# ADC.net
KiCad netlist of a schematic drawn in Altium Designer
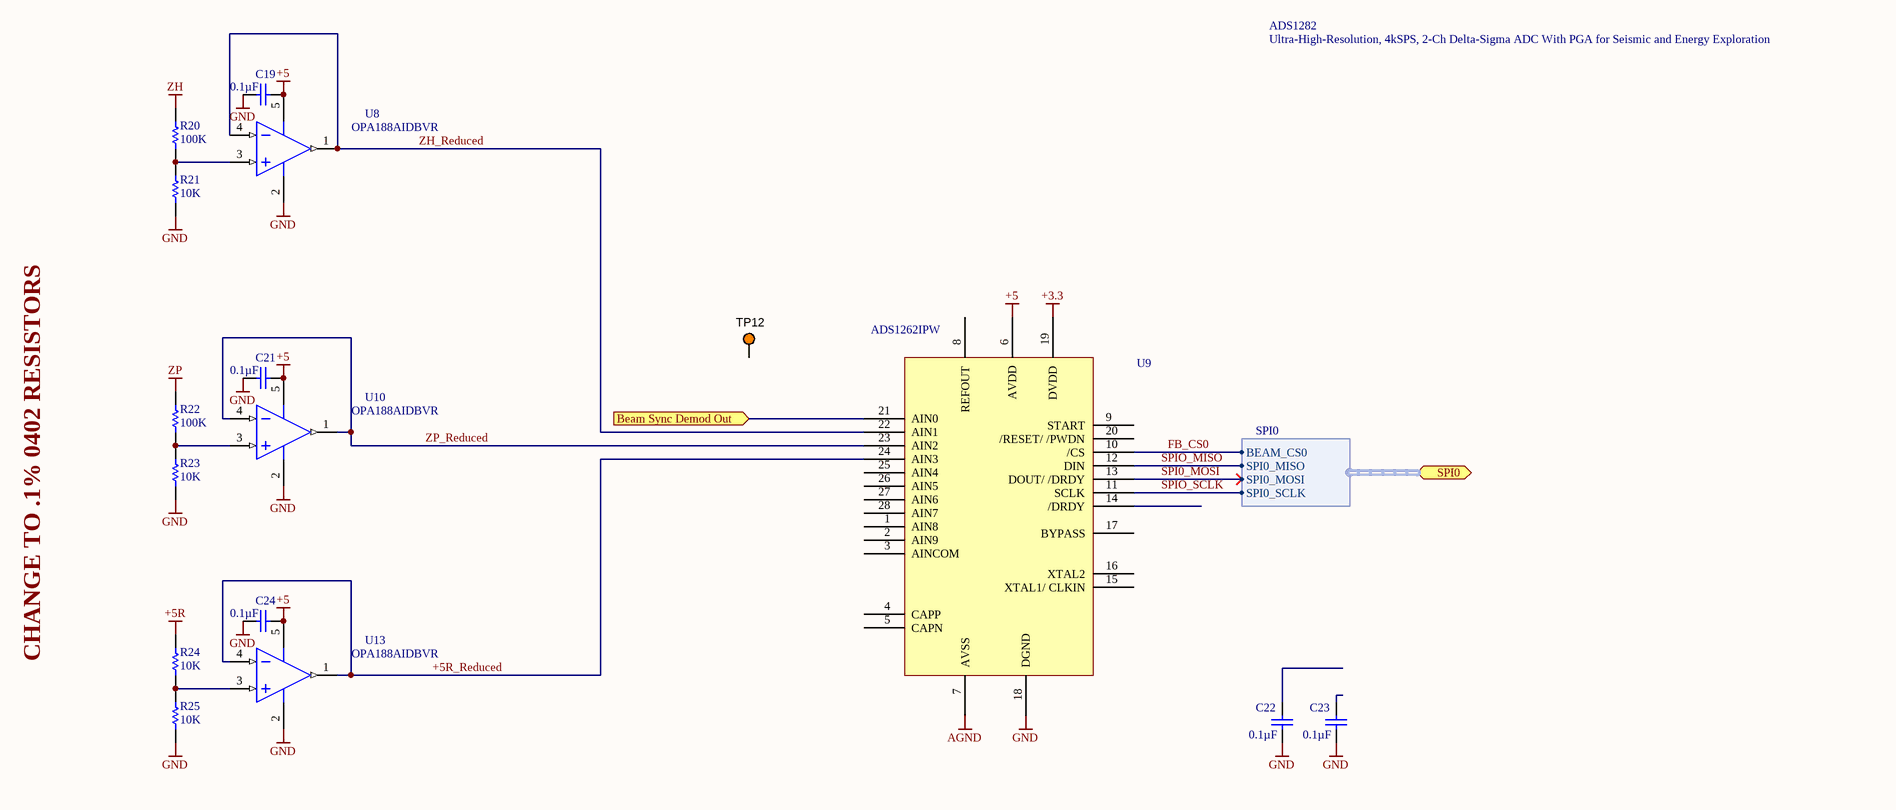
[diagram p0: ADC.SchDoc]

(export (version "E")
  (design (tool "Eeschema 10.0.6"))
  (components
    (comp (ref "C19")
      (value "CAP CER 0.1UF 25V X7R 0805")
      (footprint "CAPC0805(2012)145_N")
      (fields
        (field (name "MANUFACTURER") "Murata Electronics North America")
        (field (name "MANUFACTURER PART NUMBER") "GRM21BR71E104KA01L")
        (field (name "CAPACITANCE") "0.1µF")
        (field (name "TOLERANCE") "±10%")
      )
      (libsource (lib "Altium Content Vault") (part "CMP-1036-04795-1"))
    )
    (comp (ref "C21")
      (value "CAP CER 0.1UF 25V X7R 0805")
      (footprint "CAPC0805(2012)145_N")
      (fields
        (field (name "MANUFACTURER") "Murata Electronics North America")
        (field (name "MANUFACTURER PART NUMBER") "GRM21BR71E104KA01L")
        (field (name "CAPACITANCE") "0.1µF")
        (field (name "TOLERANCE") "±10%")
      )
      (libsource (lib "Altium Content Vault") (part "CMP-1036-04795-1"))
    )
    (comp (ref "C22")
      (value "CAP CER 0.1UF 25V X7R 0805")
      (footprint "CAPC0805(2012)145_N")
      (fields
        (field (name "MANUFACTURER") "Murata Electronics North America")
        (field (name "MANUFACTURER PART NUMBER") "GRM21BR71E104KA01L")
        (field (name "CAPACITANCE") "0.1µF")
        (field (name "TOLERANCE") "±10%")
      )
      (libsource (lib "Altium Content Vault") (part "CMP-1036-04795-1"))
    )
    (comp (ref "C23")
      (value "CAP CER 0.1UF 25V X7R 0805")
      (footprint "CAPC0805(2012)145_N")
      (fields
        (field (name "MANUFACTURER") "Murata Electronics North America")
        (field (name "MANUFACTURER PART NUMBER") "GRM21BR71E104KA01L")
        (field (name "CAPACITANCE") "0.1µF")
        (field (name "TOLERANCE") "±10%")
      )
      (libsource (lib "Altium Content Vault") (part "CMP-1036-04795-1"))
    )
    (comp (ref "C24")
      (value "CAP CER 0.1UF 25V X7R 0805")
      (footprint "CAPC0805(2012)145_N")
      (fields
        (field (name "MANUFACTURER") "Murata Electronics North America")
        (field (name "MANUFACTURER PART NUMBER") "GRM21BR71E104KA01L")
        (field (name "CAPACITANCE") "0.1µF")
        (field (name "TOLERANCE") "±10%")
      )
      (libsource (lib "Altium Content Vault") (part "CMP-1036-04795-1"))
    )
    (comp (ref "R20")
      (value "100K")
      (footprint "RESC0805(2012)_L")
      (description "RES SMD 100K OHM 1% 1/8W 0805")
      (fields
        (field (name "MANUFACTURER") "Vishay Dale")
        (field (name "MANUFACTURER PART NUMBER") "RCA0805100KFKEA")
      )
      (libsource (lib "Altium Content Vault") (part "CMP-1013-00215-1"))
    )
    (comp (ref "R21")
      (value "10K")
      (footprint "RESC0805(2012)_L")
      (description "RES SMD 10K OHM 1% 1/8W 0805")
      (fields
        (field (name "MANUFACTURER") "Vishay Dale")
        (field (name "MANUFACTURER PART NUMBER") "CRCW080510K0FKEA")
      )
      (libsource (lib "Altium Content Vault") (part "CMP-1013-00215-1"))
    )
    (comp (ref "R22")
      (value "100K")
      (footprint "RESC0805(2012)_L")
      (description "RES SMD 100K OHM 1% 1/8W 0805")
      (fields
        (field (name "MANUFACTURER") "Vishay Dale")
        (field (name "MANUFACTURER PART NUMBER") "RCA0805100KFKEA")
      )
      (libsource (lib "Altium Content Vault") (part "CMP-1013-00215-1"))
    )
    (comp (ref "R23")
      (value "10K")
      (footprint "RESC0805(2012)_L")
      (description "RES SMD 10K OHM 1% 1/8W 0805")
      (fields
        (field (name "MANUFACTURER") "Vishay Dale")
        (field (name "MANUFACTURER PART NUMBER") "CRCW080510K0FKEA")
      )
      (libsource (lib "Altium Content Vault") (part "CMP-1013-00215-1"))
    )
    (comp (ref "R24")
      (value "10K")
      (footprint "RESC0805(2012)_L")
      (description "RES SMD 10K OHM 1% 1/8W 0805")
      (fields
        (field (name "MANUFACTURER") "Vishay Dale")
        (field (name "MANUFACTURER PART NUMBER") "CRCW080510K0FKEA")
      )
      (libsource (lib "Altium Content Vault") (part "CMP-1013-00215-1"))
    )
    (comp (ref "R25")
      (value "10K")
      (footprint "RESC0805(2012)_L")
      (description "RES SMD 10K OHM 1% 1/8W 0805")
      (fields
        (field (name "MANUFACTURER") "Vishay Dale")
        (field (name "MANUFACTURER PART NUMBER") "CRCW080510K0FKEA")
      )
      (libsource (lib "Altium Content Vault") (part "CMP-1013-00215-1"))
    )
    (comp (ref "TP12")
      (value "5003")
      (footprint "KSTN-5003")
      (description "Test Point, Orange, 1-Pin THD, RoHS")
      (libsource (lib "Altium Content Vault") (part "CMP-1672-00009-1"))
    )
    (comp (ref "U8")
      (value "OPA188AIDBVR")
      (footprint "DBV0005A_M")
      (fields (field (name "MANUFACTURER") "Texas Instruments"))
      (libsource (lib "Altium Content Vault") (part "CMP-0809-00005-2"))
    )
    (comp (ref "U9")
      (value "ADS1262")
      (footprint "ADS1262")
      (description "32 bit Analog to Digital Converter")
      (fields
        (field (name "SUPPLIER PART NUMBER 1") "ADS1262IPW")
        (field (name "MANUFACTURER") "Texas Instruments")
        (field (name "MANUFACTURER PART NUMBER") "ADS1262IPW")
      )
      (libsource (lib "ZLS_Schematic_lib") (part "ADS1262"))
    )
    (comp (ref "U10")
      (value "OPA188AIDBVR")
      (footprint "DBV0005A_M")
      (fields (field (name "MANUFACTURER") "Texas Instruments"))
      (libsource (lib "Altium Content Vault") (part "CMP-0809-00005-2"))
    )
    (comp (ref "U13")
      (value "OPA188AIDBVR")
      (footprint "DBV0005A_M")
      (fields (field (name "MANUFACTURER") "Texas Instruments"))
      (libsource (lib "Altium Content Vault") (part "CMP-0809-00005-2"))
    )
  )
  (nets
    (net (code "2") (name "+3.3") (class "Default")
      (node (ref "U9") (pin "19") (pinfunction "DVDD_19") (pintype "passive"))
    )
    (net (code "3") (name "+5") (class "Default")
      (node (ref "C19") (pin "2") (pinfunction "2_2") (pintype "passive"))
      (node (ref "C21") (pin "2") (pinfunction "2_2") (pintype "passive"))
      (node (ref "C24") (pin "2") (pinfunction "2_2") (pintype "passive"))
      (node (ref "U10") (pin "5") (pinfunction "V+_5") (pintype "power_in"))
      (node (ref "U13") (pin "5") (pinfunction "V+_5") (pintype "power_in"))
      (node (ref "U8") (pin "5") (pinfunction "V+_5") (pintype "power_in"))
      (node (ref "U9") (pin "6") (pinfunction "AVDD_6") (pintype "passive"))
    )
    (net (code "4") (name "+5R") (class "Default")
      (node (ref "R24") (pin "2") (pinfunction "2_2") (pintype "passive"))
    )
    (net (code "5") (name "/+5R_Reduced") (class "Default")
      (node (ref "U13") (pin "1") (pinfunction "OUT_1") (pintype "output"))
      (node (ref "U13") (pin "4") (pinfunction "IN-_4") (pintype "input"))
      (node (ref "U9") (pin "24") (pinfunction "AIN3_24") (pintype "passive"))
    )
    (net (code "6") (name "/Beam Sync Demod Out") (class "Default")
      (node (ref "U9") (pin "21") (pinfunction "AIN0_21") (pintype "passive"))
    )
    (net (code "7") (name "/FB_CS0") (class "Default")
      (node (ref "U9") (pin "10") (pinfunction "/CS_10") (pintype "passive"))
    )
    (net (code "8") (name "/SPI0_MOSI") (class "Default")
      (node (ref "U9") (pin "13") (pinfunction "DOUT/_/DRDY_13") (pintype "passive+no_connect"))
    )
    (net (code "9") (name "/SPIO_MISO") (class "Default")
      (node (ref "U9") (pin "12") (pinfunction "DIN_12") (pintype "passive"))
    )
    (net (code "10") (name "/SPIO_SCLK") (class "Default")
      (node (ref "U9") (pin "11") (pinfunction "SCLK_11") (pintype "passive"))
    )
    (net (code "11") (name "/ZH_Reduced") (class "Default")
      (node (ref "U8") (pin "1") (pinfunction "OUT_1") (pintype "output"))
      (node (ref "U8") (pin "4") (pinfunction "IN-_4") (pintype "input"))
      (node (ref "U9") (pin "22") (pinfunction "AIN1_22") (pintype "passive"))
    )
    (net (code "12") (name "/ZP_Reduced") (class "Default")
      (node (ref "U10") (pin "1") (pinfunction "OUT_1") (pintype "output"))
      (node (ref "U10") (pin "4") (pinfunction "IN-_4") (pintype "input"))
      (node (ref "U9") (pin "23") (pinfunction "AIN2_23") (pintype "passive"))
    )
    (net (code "14") (name "AGND") (class "Default")
      (node (ref "U9") (pin "7") (pinfunction "AVSS_7") (pintype "passive"))
    )
    (net (code "15") (name "GND") (class "Default")
      (node (ref "C19") (pin "1") (pinfunction "1_1") (pintype "passive"))
      (node (ref "C21") (pin "1") (pinfunction "1_1") (pintype "passive"))
      (node (ref "C22") (pin "2") (pinfunction "2_2") (pintype "passive"))
      (node (ref "C23") (pin "2") (pinfunction "2_2") (pintype "passive"))
      (node (ref "C24") (pin "1") (pinfunction "1_1") (pintype "passive"))
      (node (ref "R21") (pin "1") (pinfunction "1_1") (pintype "passive"))
      (node (ref "R23") (pin "1") (pinfunction "1_1") (pintype "passive"))
      (node (ref "R25") (pin "1") (pinfunction "1_1") (pintype "passive"))
      (node (ref "U10") (pin "2") (pinfunction "V-_2") (pintype "power_in"))
      (node (ref "U13") (pin "2") (pinfunction "V-_2") (pintype "power_in"))
      (node (ref "U8") (pin "2") (pinfunction "V-_2") (pintype "power_in"))
      (node (ref "U9") (pin "18") (pinfunction "DGND_18") (pintype "passive"))
    )
    (net (code "16") (name "Net-(U8-IN+)") (class "Default")
      (node (ref "R20") (pin "1") (pinfunction "1_1") (pintype "passive"))
      (node (ref "R21") (pin "2") (pinfunction "2_2") (pintype "passive"))
      (node (ref "U8") (pin "3") (pinfunction "IN+_3") (pintype "input"))
    )
    (net (code "17") (name "Net-(U10-IN+)") (class "Default")
      (node (ref "R22") (pin "1") (pinfunction "1_1") (pintype "passive"))
      (node (ref "R23") (pin "2") (pinfunction "2_2") (pintype "passive"))
      (node (ref "U10") (pin "3") (pinfunction "IN+_3") (pintype "input"))
    )
    (net (code "18") (name "Net-(U13-IN+)") (class "Default")
      (node (ref "R24") (pin "1") (pinfunction "1_1") (pintype "passive"))
      (node (ref "R25") (pin "2") (pinfunction "2_2") (pintype "passive"))
      (node (ref "U13") (pin "3") (pinfunction "IN+_3") (pintype "input"))
    )
    (net (code "19") (name "ZH") (class "Default")
      (node (ref "R20") (pin "2") (pinfunction "2_2") (pintype "passive"))
    )
    (net (code "20") (name "ZP") (class "Default")
      (node (ref "R22") (pin "2") (pinfunction "2_2") (pintype "passive"))
    )
    (net (code "21") (name "unconnected-(C22-Pad1)") (class "Default")
      (node (ref "C22") (pin "1") (pinfunction "1_1") (pintype "passive"))
    )
    (net (code "22") (name "unconnected-(C23-Pad1)") (class "Default")
      (node (ref "C23") (pin "1") (pinfunction "1_1") (pintype "passive"))
    )
    (net (code "23") (name "unconnected-(TP12-Pad1)") (class "Default")
      (node (ref "TP12") (pin "1") (pinfunction "1_1") (pintype "passive"))
    )
    (net (code "24") (name "unconnected-(U9-AIN4-Pad25)") (class "Default")
      (node (ref "U9") (pin "25") (pinfunction "AIN4_25") (pintype "passive"))
    )
    (net (code "25") (name "unconnected-(U9-AIN5-Pad26)") (class "Default")
      (node (ref "U9") (pin "26") (pinfunction "AIN5_26") (pintype "passive"))
    )
    (net (code "26") (name "unconnected-(U9-AIN6-Pad27)") (class "Default")
      (node (ref "U9") (pin "27") (pinfunction "AIN6_27") (pintype "passive"))
    )
    (net (code "27") (name "unconnected-(U9-AIN7-Pad28)") (class "Default")
      (node (ref "U9") (pin "28") (pinfunction "AIN7_28") (pintype "passive"))
    )
    (net (code "28") (name "unconnected-(U9-AIN8-Pad1)") (class "Default")
      (node (ref "U9") (pin "1") (pinfunction "AIN8_1") (pintype "passive"))
    )
    (net (code "29") (name "unconnected-(U9-AIN9-Pad2)") (class "Default")
      (node (ref "U9") (pin "2") (pinfunction "AIN9_2") (pintype "passive"))
    )
    (net (code "30") (name "unconnected-(U9-AINCOM-Pad3)") (class "Default")
      (node (ref "U9") (pin "3") (pinfunction "AINCOM_3") (pintype "passive"))
    )
    (net (code "31") (name "unconnected-(U9-BYPASS-Pad17)") (class "Default")
      (node (ref "U9") (pin "17") (pinfunction "BYPASS_17") (pintype "passive"))
    )
    (net (code "32") (name "unconnected-(U9-CAPN-Pad5)") (class "Default")
      (node (ref "U9") (pin "5") (pinfunction "CAPN_5") (pintype "passive"))
    )
    (net (code "33") (name "unconnected-(U9-CAPP-Pad4)") (class "Default")
      (node (ref "U9") (pin "4") (pinfunction "CAPP_4") (pintype "passive"))
    )
    (net (code "34") (name "unconnected-(U9-REFOUT-Pad8)") (class "Default")
      (node (ref "U9") (pin "8") (pinfunction "REFOUT_8") (pintype "passive"))
    )
    (net (code "35") (name "unconnected-(U9-START-Pad9)") (class "Default")
      (node (ref "U9") (pin "9") (pinfunction "START_9") (pintype "passive"))
    )
    (net (code "36") (name "unconnected-(U9-XTAL1{slash}_CLKIN-Pad15)") (class "Default")
      (node (ref "U9") (pin "15") (pinfunction "XTAL1/_CLKIN_15") (pintype "passive"))
    )
    (net (code "37") (name "unconnected-(U9-XTAL2-Pad16)") (class "Default")
      (node (ref "U9") (pin "16") (pinfunction "XTAL2_16") (pintype "passive"))
    )
    (net (code "38") (name "unconnected-(U9-{slash}DRDY-Pad14)") (class "Default")
      (node (ref "U9") (pin "14") (pinfunction "/DRDY_14") (pintype "passive"))
    )
    (net (code "39") (name "unconnected-(U9-{slash}RESET{slash}_{slash}PWDN-Pad20)") (class "Default")
      (node (ref "U9") (pin "20") (pinfunction "/RESET/_/PWDN_20") (pintype "passive"))
    )
  )
)
